# 400vMonitor.net
KiCad netlist of a schematic drawn in Altium Designer
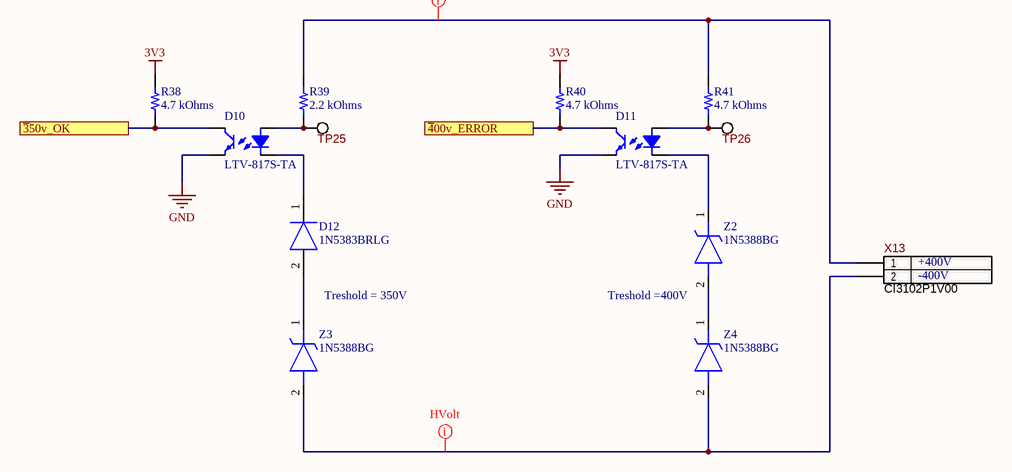
[diagram p0: 400vMonitor.SchDoc]

(export (version "E")
  (design (tool "Eeschema 10.0.6"))
  (components
    (comp (ref "D10")
      (value "LTV-817S-TA")
      (footprint "LITEON LTV-817")
      (description "OPTOISOLATR 5KV TRANSISTOR 4-SMD")
      (fields (field (name "MANUFACTURER") "Lite-On Inc."))
      (libsource (lib "Celestial Altium Library - altium_library") (part "Optoisolator"))
    )
    (comp (ref "D11")
      (value "LTV-817S-TA")
      (footprint "LITEON LTV-817")
      (description "OPTOISOLATR 5KV TRANSISTOR 4-SMD")
      (fields (field (name "MANUFACTURER") "Lite-On Inc."))
      (libsource (lib "Celestial Altium Library - altium_library") (part "Optoisolator"))
    )
    (comp (ref "D12")
      (value "1N5383BRLG")
      (footprint "SamacSys:DIOAD2260W109L864D349")
      (description "Diode")
      (fields (field (name "MOUSER PART NUMBER") "863-1N5383BRLG"))
      (libsource (lib "*") (part "1N5383BRLG"))
    )
    (comp (ref "R38")
      (value "4.7 kOhms")
      (footprint "RES 0805_2012")
      (description "RES SMD 4.7K OHM 5% 0.4W 0805")
      (fields (field (name "PART NUMBER") "RCS08054K70JNEA") (field (name "MANUFACTURER") "Vishay Dale"))
      (libsource (lib "Celestial Altium Library - altium_library") (part "Resistor"))
    )
    (comp (ref "R39")
      (value "2.2 kOhms")
      (footprint "RES 0805_2012")
      (description "RES SMD 2.2K OHM 5% 1/4W 0805")
      (fields (field (name "PART NUMBER") "SR0805JR-7W2K2L") (field (name "MANUFACTURER") "Yageo"))
      (libsource (lib "Celestial Altium Library - altium_library") (part "Resistor"))
    )
    (comp (ref "R40")
      (value "4.7 kOhms")
      (footprint "RES 0805_2012")
      (description "RES SMD 4.7K OHM 5% 0.4W 0805")
      (fields (field (name "PART NUMBER") "RCS08054K70JNEA") (field (name "MANUFACTURER") "Vishay Dale"))
      (libsource (lib "Celestial Altium Library - altium_library") (part "Resistor"))
    )
    (comp (ref "R41")
      (value "4.7 kOhms")
      (footprint "RES 0805_2012")
      (description "RES SMD 4.7K OHM 5% 0.4W 0805")
      (fields (field (name "PART NUMBER") "RCS08054K70JNEA") (field (name "MANUFACTURER") "Vishay Dale"))
      (libsource (lib "Celestial Altium Library - altium_library") (part "Resistor"))
    )
    (comp (ref "TP25")
      (value "PAD-1.1mm")
      (footprint "PAD-1.1mm")
      (description "1.1mm Pad for Plug-In or Receptacle")
      (fields (field (name "MANUFACTURER") "NONE"))
      (libsource (lib "misc") (part "PAD-1.1mm"))
    )
    (comp (ref "TP26")
      (value "PAD-1.1mm")
      (footprint "PAD-1.1mm")
      (description "1.1mm Pad for Plug-In or Receptacle")
      (fields (field (name "MANUFACTURER") "NONE"))
      (libsource (lib "misc") (part "PAD-1.1mm"))
    )
    (comp (ref "X13")
      (value "WH-02S")
      (footprint "WF-2S")
      (description "WH Series 2.54mm Wire to Board Straight DIP Type Headers, 2 Pin")
      (fields (field (name "PART NUMBER") "CI3102P1V00") (field (name "MANUFACTURER") "CviLux"))
      (libsource (lib "Connectors") (part "CI3102P1V00"))
    )
    (comp (ref "Z2")
      (value "1N5388BG")
      (footprint "SamacSys:DIOAD2260W109L864D349")
      (description "Zener Diode")
      (fields (field (name "MOUSER PART NUMBER") "863-1N5388BG"))
      (libsource (lib "*") (part "1N5388BG"))
    )
    (comp (ref "Z3")
      (value "1N5388BG")
      (footprint "SamacSys:DIOAD2260W109L864D349")
      (description "Zener Diode")
      (fields (field (name "MOUSER PART NUMBER") "863-1N5388BG"))
      (libsource (lib "*") (part "1N5388BG"))
    )
    (comp (ref "Z4")
      (value "1N5388BG")
      (footprint "SamacSys:DIOAD2260W109L864D349")
      (description "Zener Diode")
      (fields (field (name "MOUSER PART NUMBER") "863-1N5388BG"))
      (libsource (lib "*") (part "1N5388BG"))
    )
  )
  (nets
    (net (code "1") (name "/~{3}50v_OK") (class "Default")
      (node (ref "D10") (pin "4") (pinfunction "4_4") (pintype "passive"))
      (node (ref "R38") (pin "1") (pinfunction "1_1") (pintype "passive"))
    )
    (net (code "2") (name "/~{4}00v_ERROR") (class "Default")
      (node (ref "D11") (pin "4") (pinfunction "4_4") (pintype "passive"))
      (node (ref "R40") (pin "1") (pinfunction "1_1") (pintype "passive"))
    )
    (net (code "3") (name "3V3") (class "Default")
      (node (ref "R38") (pin "2") (pinfunction "2_2") (pintype "passive"))
      (node (ref "R40") (pin "2") (pinfunction "2_2") (pintype "passive"))
    )
    (net (code "4") (name "GND") (class "Default")
      (node (ref "D10") (pin "3") (pinfunction "3_3") (pintype "passive"))
      (node (ref "D11") (pin "3") (pinfunction "3_3") (pintype "passive"))
    )
    (net (code "5") (name "Net-(D10-Pad1)") (class "Default")
      (node (ref "D10") (pin "1") (pinfunction "1_1") (pintype "passive"))
      (node (ref "R39") (pin "1") (pinfunction "1_1") (pintype "passive"))
      (node (ref "TP25") (pin "1") (pintype "passive"))
    )
    (net (code "6") (name "Net-(D11-Pad1)") (class "Default")
      (node (ref "D11") (pin "1") (pinfunction "1_1") (pintype "passive"))
      (node (ref "R41") (pin "1") (pinfunction "1_1") (pintype "passive"))
      (node (ref "TP26") (pin "1") (pintype "passive"))
    )
    (net (code "7") (name "Net-(D12-A)") (class "Default")
      (node (ref "D12") (pin "2") (pinfunction "A_2") (pintype "passive"))
      (node (ref "Z3") (pin "1") (pinfunction "K_1") (pintype "passive"))
    )
    (net (code "8") (name "Net-(D12-K)") (class "Default")
      (node (ref "D10") (pin "2") (pinfunction "2_2") (pintype "passive"))
      (node (ref "D12") (pin "1") (pinfunction "K_1") (pintype "passive"))
    )
    (net (code "9") (name "Net-(R39-Pad2)") (class "Default")
      (node (ref "R39") (pin "2") (pinfunction "2_2") (pintype "passive"))
      (node (ref "R41") (pin "2") (pinfunction "2_2") (pintype "passive"))
      (node (ref "X13") (pin "1") (pinfunction "1_1") (pintype "passive"))
    )
    (net (code "10") (name "Net-(Z2-A)") (class "Default")
      (node (ref "Z2") (pin "2") (pinfunction "A_2") (pintype "passive"))
      (node (ref "Z4") (pin "1") (pinfunction "K_1") (pintype "passive"))
    )
    (net (code "11") (name "Net-(Z2-K)") (class "Default")
      (node (ref "D11") (pin "2") (pinfunction "2_2") (pintype "passive"))
      (node (ref "Z2") (pin "1") (pinfunction "K_1") (pintype "passive"))
    )
    (net (code "12") (name "Net-(Z3-A)") (class "Default")
      (node (ref "X13") (pin "2") (pinfunction "2_2") (pintype "passive"))
      (node (ref "Z3") (pin "2") (pinfunction "A_2") (pintype "passive"))
      (node (ref "Z4") (pin "2") (pinfunction "A_2") (pintype "passive"))
    )
  )
)
